# MA-Mosaic.net
KiCad netlist of a schematic drawn in Altium Designer
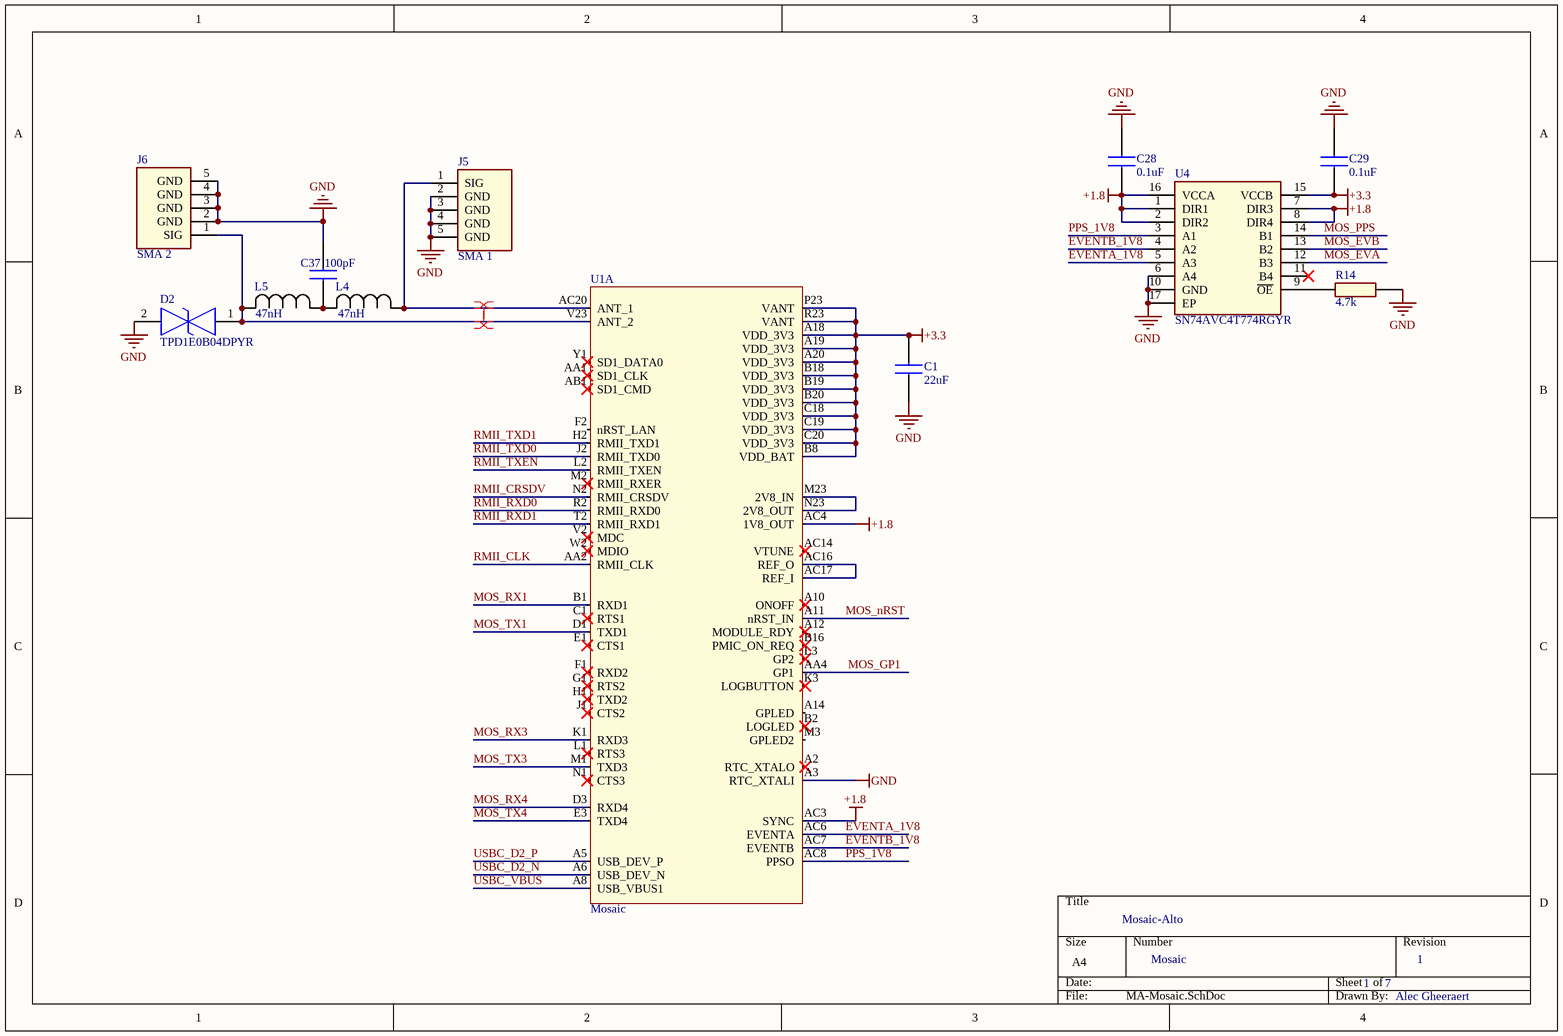
[diagram p0: MA-Mosaic.SchDoc]

(export (version "E")
  (design (tool "Eeschema 10.0.6"))
  (components
    (comp (ref "C1")
      (value "22uF")
      (footprint "CAPC2012X145N")
      (description "0805 22µF")
      (fields (field (name "MANUFACTURER") "Walsin") (field (name "TOLERANCE") "10%"))
      (libsource (lib "Ghrt") (part "0805X226K6R3CT"))
    )
    (comp (ref "C28")
      (value "0.1uF")
      (footprint "CAPC1005X55N")
      (description "0402I 0.1µF")
      (fields (field (name "MANUFACTURER") "Walsin") (field (name "TOLERANCE") "10%"))
      (libsource (lib "Ghrt") (part "MG15B104K100CT"))
    )
    (comp (ref "C29")
      (value "0.1uF")
      (footprint "CAPC1005X55N")
      (description "0402I 0.1µF")
      (fields (field (name "MANUFACTURER") "Walsin") (field (name "TOLERANCE") "10%"))
      (libsource (lib "Ghrt") (part "MG15B104K100CT"))
    )
    (comp (ref "C37")
      (value "100pF")
      (footprint "CAPC0603X35N")
      (description "0201 100pF")
      (libsource (lib "Ghrt") (part "0201N101J250CT"))
    )
    (comp (ref "D2")
      (value "TPD1E0B04DPYR")
      (footprint "TPD1E0B04DPYR")
      (description "1 Channel TVS Diode")
      (libsource (lib "Ghrt") (part "TPD1E0B04DPYR"))
    )
    (comp (ref "J5")
      (value "SMA 1")
      (footprint "3-1478978-1")
      (description "RF SMA Connector")
      (libsource (lib "") (part "3-1478978-1_1"))
    )
    (comp (ref "J6")
      (value "SMA 2")
      (footprint "3-1478978-1")
      (description "RF SMA Connector")
      (libsource (lib "Ghrt") (part "3-1478978-1"))
    )
    (comp (ref "L4")
      (value "47nH")
      (footprint "IND_1005_TDK")
      (description "47nH 1.4GHz Inductor")
      (libsource (lib "Ghrt") (part "MLG1005S47NJTD25"))
    )
    (comp (ref "L5")
      (value "47nH")
      (footprint "IND_1005_TDK")
      (description "47nH 1.4GHz Inductor")
      (libsource (lib "Ghrt") (part "MLG1005S47NJTD25"))
    )
    (comp (ref "R14")
      (value "4.7k")
      (footprint "RESC1005X40N")
      (description "0402I 4.7k")
      (fields (field (name "MANUFACTURER") "Walsin") (field (name "TOLERANCE") "1%"))
      (libsource (lib "Ghrt") (part "WR04X4701FTL"))
    )
    (comp (ref "U1")
      (value "Mosaic")
      (footprint "Mosaic")
      (description "GNSS RTK Receiver")
      (fields (field (name "MANUFACTURER") "Septentrio"))
      (libsource (lib "Ghrt") (part "CMP-00013-3"))
    )
    (comp (ref "U4")
      (value "SN74AVC4T774RGYR")
      (footprint "SN74AVC4T774RGYR")
      (description "4B Dual-Supply Level Shifter")
      (fields (field (name "MANUFACTURER") "Texas Instruments"))
      (libsource (lib "Ghrt") (part "SN74AVC4T774RGYR"))
    )
  )
  (nets
    (net (code "1") (name "+1.8") (class "Default")
      (node (ref "C28") (pin "1") (pinfunction "1_1") (pintype "passive"))
      (node (ref "U1") (pin "AC3") (pinfunction "SYNC_AC3") (pintype "input"))
      (node (ref "U1") (pin "AC4") (pinfunction "1V8_OUT_AC4") (pintype "power_in"))
      (node (ref "U4") (pin "1") (pinfunction "DIR1_1") (pintype "passive"))
      (node (ref "U4") (pin "16") (pinfunction "VCCA_16") (pintype "passive"))
      (node (ref "U4") (pin "2") (pinfunction "DIR2_2") (pintype "passive"))
      (node (ref "U4") (pin "7") (pinfunction "DIR3_7") (pintype "passive"))
      (node (ref "U4") (pin "8") (pinfunction "DIR4_8") (pintype "passive"))
    )
    (net (code "2") (name "+3.3") (class "Default")
      (node (ref "C1") (pin "1") (pinfunction "1_1") (pintype "passive"))
      (node (ref "C29") (pin "1") (pinfunction "1_1") (pintype "passive"))
      (node (ref "U1") (pin "A18") (pinfunction "VDD_3V3_A18") (pintype "power_in"))
      (node (ref "U1") (pin "A19") (pinfunction "VDD_3V3_A19") (pintype "power_in"))
      (node (ref "U1") (pin "A20") (pinfunction "VDD_3V3_A20") (pintype "power_in"))
      (node (ref "U1") (pin "B18") (pinfunction "VDD_3V3_B18") (pintype "power_in"))
      (node (ref "U1") (pin "B19") (pinfunction "VDD_3V3_B19") (pintype "power_in"))
      (node (ref "U1") (pin "B20") (pinfunction "VDD_3V3_B20") (pintype "power_in"))
      (node (ref "U1") (pin "B8") (pinfunction "VDD_BAT_B8") (pintype "power_in"))
      (node (ref "U1") (pin "C18") (pinfunction "VDD_3V3_C18") (pintype "power_in"))
      (node (ref "U1") (pin "C19") (pinfunction "VDD_3V3_C19") (pintype "power_in"))
      (node (ref "U1") (pin "C20") (pinfunction "VDD_3V3_C20") (pintype "power_in"))
      (node (ref "U1") (pin "P23") (pinfunction "VANT_P23") (pintype "power_in"))
      (node (ref "U1") (pin "R23") (pinfunction "VANT_R23") (pintype "power_in"))
      (node (ref "U4") (pin "15") (pinfunction "VCCB_15") (pintype "passive"))
    )
    (net (code "3") (name "/EVENTA_1V8") (class "Default")
      (node (ref "U1") (pin "AC6") (pinfunction "EVENTA_AC6") (pintype "input"))
      (node (ref "U4") (pin "5") (pinfunction "A3_5") (pintype "passive"))
    )
    (net (code "4") (name "/EVENTB_1V8") (class "Default")
      (node (ref "U1") (pin "AC7") (pinfunction "EVENTB_AC7") (pintype "input"))
      (node (ref "U4") (pin "4") (pinfunction "A2_4") (pintype "passive"))
    )
    (net (code "5") (name "/MOS_EVA") (class "Default")
      (node (ref "U4") (pin "12") (pinfunction "B3_12") (pintype "passive"))
    )
    (net (code "6") (name "/MOS_EVB") (class "Default")
      (node (ref "U4") (pin "13") (pinfunction "B2_13") (pintype "passive"))
    )
    (net (code "7") (name "/MOS_GP1") (class "Default")
      (node (ref "U1") (pin "AA4") (pinfunction "GP1_AA4") (pintype "output"))
    )
    (net (code "8") (name "/MOS_PPS") (class "Default")
      (node (ref "U4") (pin "14") (pinfunction "B1_14") (pintype "passive"))
    )
    (net (code "9") (name "/MOS_RX1") (class "Default")
      (node (ref "U1") (pin "B1") (pinfunction "RXD1_B1") (pintype "input"))
    )
    (net (code "10") (name "/MOS_RX3") (class "Default")
      (node (ref "U1") (pin "K1") (pinfunction "RXD3_K1") (pintype "input"))
    )
    (net (code "11") (name "/MOS_RX4") (class "Default")
      (node (ref "U1") (pin "D3") (pinfunction "RXD4_D3") (pintype "input"))
    )
    (net (code "12") (name "/MOS_TX1") (class "Default")
      (node (ref "U1") (pin "D1") (pinfunction "TXD1_D1") (pintype "output"))
    )
    (net (code "13") (name "/MOS_TX3") (class "Default")
      (node (ref "U1") (pin "M1") (pinfunction "TXD3_M1") (pintype "output"))
    )
    (net (code "14") (name "/MOS_TX4") (class "Default")
      (node (ref "U1") (pin "E3") (pinfunction "TXD4_E3") (pintype "output"))
    )
    (net (code "15") (name "/MOS_nRST") (class "Default")
      (node (ref "U1") (pin "A11") (pinfunction "nRST_IN_A11") (pintype "input"))
    )
    (net (code "16") (name "/PPS_1V8") (class "Default")
      (node (ref "U1") (pin "AC8") (pinfunction "PPSO_AC8") (pintype "output"))
      (node (ref "U4") (pin "3") (pinfunction "A1_3") (pintype "passive"))
    )
    (net (code "17") (name "/RMII_CLK") (class "Default")
      (node (ref "U1") (pin "AA2") (pinfunction "RMII_CLK_AA2") (pintype "output"))
    )
    (net (code "18") (name "/RMII_CRSDV") (class "Default")
      (node (ref "U1") (pin "N2") (pinfunction "RMII_CRSDV_N2") (pintype "input"))
    )
    (net (code "19") (name "/RMII_RXD0") (class "Default")
      (node (ref "U1") (pin "R2") (pinfunction "RMII_RXD0_R2") (pintype "input"))
    )
    (net (code "20") (name "/RMII_RXD1") (class "Default")
      (node (ref "U1") (pin "T2") (pinfunction "RMII_RXD1_T2") (pintype "input"))
    )
    (net (code "21") (name "/RMII_TXD0") (class "Default")
      (node (ref "U1") (pin "J2") (pinfunction "RMII_TXD0_J2") (pintype "output"))
    )
    (net (code "22") (name "/RMII_TXD1") (class "Default")
      (node (ref "U1") (pin "H2") (pinfunction "RMII_TXD1_H2") (pintype "output"))
    )
    (net (code "23") (name "/RMII_TXEN") (class "Default")
      (node (ref "U1") (pin "L2") (pinfunction "RMII_TXEN_L2") (pintype "output"))
    )
    (net (code "24") (name "/USBC_D2_N") (class "Default")
      (node (ref "U1") (pin "A6") (pinfunction "USB_DEV_N_A6") (pintype "bidirectional"))
    )
    (net (code "25") (name "/USBC_D2_P") (class "Default")
      (node (ref "U1") (pin "A5") (pinfunction "USB_DEV_P_A5") (pintype "bidirectional"))
    )
    (net (code "26") (name "/USBC_VBUS") (class "Default")
      (node (ref "U1") (pin "A8") (pinfunction "USB_VBUS1_A8") (pintype "power_in"))
    )
    (net (code "27") (name "GND") (class "Default")
      (node (ref "C1") (pin "2") (pinfunction "2_2") (pintype "passive"))
      (node (ref "C28") (pin "2") (pinfunction "2_2") (pintype "passive"))
      (node (ref "C29") (pin "2") (pinfunction "2_2") (pintype "passive"))
      (node (ref "C37") (pin "2") (pinfunction "2_2") (pintype "passive"))
      (node (ref "D2") (pin "2") (pinfunction "2_2") (pintype "passive"))
      (node (ref "J5") (pin "2") (pinfunction "GND_2") (pintype "passive"))
      (node (ref "J5") (pin "3") (pinfunction "GND_3") (pintype "passive"))
      (node (ref "J5") (pin "4") (pinfunction "GND_4") (pintype "passive"))
      (node (ref "J5") (pin "5") (pinfunction "GND_5") (pintype "passive"))
      (node (ref "J6") (pin "2") (pinfunction "GND_2") (pintype "passive"))
      (node (ref "J6") (pin "3") (pinfunction "GND_3") (pintype "passive"))
      (node (ref "J6") (pin "4") (pinfunction "GND_4") (pintype "passive"))
      (node (ref "J6") (pin "5") (pinfunction "GND_5") (pintype "passive"))
      (node (ref "R14") (pin "2") (pinfunction "2_2") (pintype "passive"))
      (node (ref "U1") (pin "A3") (pinfunction "RTC_XTALI_A3") (pintype "input"))
      (node (ref "U4") (pin "10") (pinfunction "GND_10") (pintype "passive"))
      (node (ref "U4") (pin "17") (pinfunction "EP_17") (pintype "passive"))
      (node (ref "U4") (pin "6") (pinfunction "A4_6") (pintype "passive"))
    )
    (net (code "28") (name "Net-(C37-Pad1)") (class "Default")
      (node (ref "C37") (pin "1") (pinfunction "1_1") (pintype "passive"))
      (node (ref "L4") (pin "2") (pinfunction "2_2") (pintype "passive"))
      (node (ref "L5") (pin "1") (pinfunction "1_1") (pintype "passive"))
    )
    (net (code "29") (name "Net-(J5-SIG)") (class "Default")
      (node (ref "J5") (pin "1") (pinfunction "SIG_1") (pintype "passive"))
      (node (ref "L4") (pin "1") (pinfunction "1_1") (pintype "passive"))
      (node (ref "U1") (pin "AC20") (pinfunction "ANT_1_AC20") (pintype "input"))
    )
    (net (code "30") (name "Net-(J6-SIG)") (class "Default")
      (node (ref "D2") (pin "1") (pinfunction "1_1") (pintype "passive"))
      (node (ref "J6") (pin "1") (pinfunction "SIG_1") (pintype "passive"))
      (node (ref "L5") (pin "2") (pinfunction "2_2") (pintype "passive"))
      (node (ref "U1") (pin "V23") (pinfunction "ANT_2_V23") (pintype "input"))
    )
    (net (code "31") (name "Net-(U1A-2V8_IN)") (class "Default")
      (node (ref "U1") (pin "M23") (pinfunction "2V8_IN_M23") (pintype "power_in"))
      (node (ref "U1") (pin "N23") (pinfunction "2V8_OUT_N23") (pintype "power_in"))
    )
    (net (code "32") (name "Net-(U1A-REF_I)") (class "Default")
      (node (ref "U1") (pin "AC16") (pinfunction "REF_O_AC16") (pintype "output"))
      (node (ref "U1") (pin "AC17") (pinfunction "REF_I_AC17") (pintype "input"))
    )
    (net (code "33") (name "Net-(U4-~{OE})") (class "Default")
      (node (ref "R14") (pin "1") (pinfunction "1_1") (pintype "passive"))
      (node (ref "U4") (pin "9") (pinfunction "~{OE}_9") (pintype "passive"))
    )
    (net (code "34") (name "unconnected-(U1A-CTS1-PadE1)") (class "Default")
      (node (ref "U1") (pin "E1") (pinfunction "CTS1_E1") (pintype "input+no_connect"))
    )
    (net (code "35") (name "unconnected-(U1A-CTS2-PadJ1)") (class "Default")
      (node (ref "U1") (pin "J1") (pinfunction "CTS2_J1") (pintype "input+no_connect"))
    )
    (net (code "36") (name "unconnected-(U1A-CTS3-PadN1)") (class "Default")
      (node (ref "U1") (pin "N1") (pinfunction "CTS3_N1") (pintype "input+no_connect"))
    )
    (net (code "37") (name "unconnected-(U1A-GP2-PadL3)") (class "Default")
      (node (ref "U1") (pin "L3") (pinfunction "GP2_L3") (pintype "output+no_connect"))
    )
    (net (code "38") (name "unconnected-(U1A-GPLED-PadA14)") (class "Default")
      (node (ref "U1") (pin "A14") (pinfunction "GPLED_A14") (pintype "output"))
    )
    (net (code "39") (name "unconnected-(U1A-GPLED2-PadM3)") (class "Default")
      (node (ref "U1") (pin "M3") (pinfunction "GPLED2_M3") (pintype "output"))
    )
    (net (code "40") (name "unconnected-(U1A-LOGBUTTON-PadK3)") (class "Default")
      (node (ref "U1") (pin "K3") (pinfunction "LOGBUTTON_K3") (pintype "input+no_connect"))
    )
    (net (code "41") (name "unconnected-(U1A-LOGLED-PadB2)") (class "Default")
      (node (ref "U1") (pin "B2") (pinfunction "LOGLED_B2") (pintype "output+no_connect"))
    )
    (net (code "42") (name "unconnected-(U1A-MDC-PadV2)") (class "Default")
      (node (ref "U1") (pin "V2") (pinfunction "MDC_V2") (pintype "output+no_connect"))
    )
    (net (code "43") (name "unconnected-(U1A-MDIO-PadW2)") (class "Default")
      (node (ref "U1") (pin "W2") (pinfunction "MDIO_W2") (pintype "bidirectional+no_connect"))
    )
    (net (code "44") (name "unconnected-(U1A-MODULE_RDY-PadA12)") (class "Default")
      (node (ref "U1") (pin "A12") (pinfunction "MODULE_RDY_A12") (pintype "output+no_connect"))
    )
    (net (code "45") (name "unconnected-(U1A-ONOFF-PadA10)") (class "Default")
      (node (ref "U1") (pin "A10") (pinfunction "ONOFF_A10") (pintype "input+no_connect"))
    )
    (net (code "46") (name "unconnected-(U1A-PMIC_ON_REQ-PadB16)") (class "Default")
      (node (ref "U1") (pin "B16") (pinfunction "PMIC_ON_REQ_B16") (pintype "output+no_connect"))
    )
    (net (code "47") (name "unconnected-(U1A-RMII_RXER-PadM2)") (class "Default")
      (node (ref "U1") (pin "M2") (pinfunction "RMII_RXER_M2") (pintype "input+no_connect"))
    )
    (net (code "48") (name "unconnected-(U1A-RTC_XTALO-PadA2)") (class "Default")
      (node (ref "U1") (pin "A2") (pinfunction "RTC_XTALO_A2") (pintype "output+no_connect"))
    )
    (net (code "49") (name "unconnected-(U1A-RTS1-PadC1)") (class "Default")
      (node (ref "U1") (pin "C1") (pinfunction "RTS1_C1") (pintype "output+no_connect"))
    )
    (net (code "50") (name "unconnected-(U1A-RTS2-PadG1)") (class "Default")
      (node (ref "U1") (pin "G1") (pinfunction "RTS2_G1") (pintype "output+no_connect"))
    )
    (net (code "51") (name "unconnected-(U1A-RTS3-PadL1)") (class "Default")
      (node (ref "U1") (pin "L1") (pinfunction "RTS3_L1") (pintype "output+no_connect"))
    )
    (net (code "52") (name "unconnected-(U1A-RXD2-PadF1)") (class "Default")
      (node (ref "U1") (pin "F1") (pinfunction "RXD2_F1") (pintype "input+no_connect"))
    )
    (net (code "53") (name "unconnected-(U1A-SD1_CLK-PadAA1)") (class "Default")
      (node (ref "U1") (pin "AA1") (pinfunction "SD1_CLK_AA1") (pintype "output+no_connect"))
    )
    (net (code "54") (name "unconnected-(U1A-SD1_CMD-PadAB1)") (class "Default")
      (node (ref "U1") (pin "AB1") (pinfunction "SD1_CMD_AB1") (pintype "output+no_connect"))
    )
    (net (code "55") (name "unconnected-(U1A-SD1_DATA0-PadY1)") (class "Default")
      (node (ref "U1") (pin "Y1") (pinfunction "SD1_DATA0_Y1") (pintype "bidirectional+no_connect"))
    )
    (net (code "56") (name "unconnected-(U1A-TXD2-PadH1)") (class "Default")
      (node (ref "U1") (pin "H1") (pinfunction "TXD2_H1") (pintype "output+no_connect"))
    )
    (net (code "57") (name "unconnected-(U1A-VTUNE-PadAC14)") (class "Default")
      (node (ref "U1") (pin "AC14") (pinfunction "VTUNE_AC14") (pintype "input+no_connect"))
    )
    (net (code "58") (name "unconnected-(U1A-nRST_LAN-PadF2)") (class "Default")
      (node (ref "U1") (pin "F2") (pinfunction "nRST_LAN_F2") (pintype "output"))
    )
    (net (code "59") (name "unconnected-(U4-B4-Pad11)") (class "Default")
      (node (ref "U4") (pin "11") (pinfunction "B4_11") (pintype "passive+no_connect"))
    )
  )
)
